# DIMM_CONNECTOR.net
KiCad netlist of a schematic drawn in Altium Designer
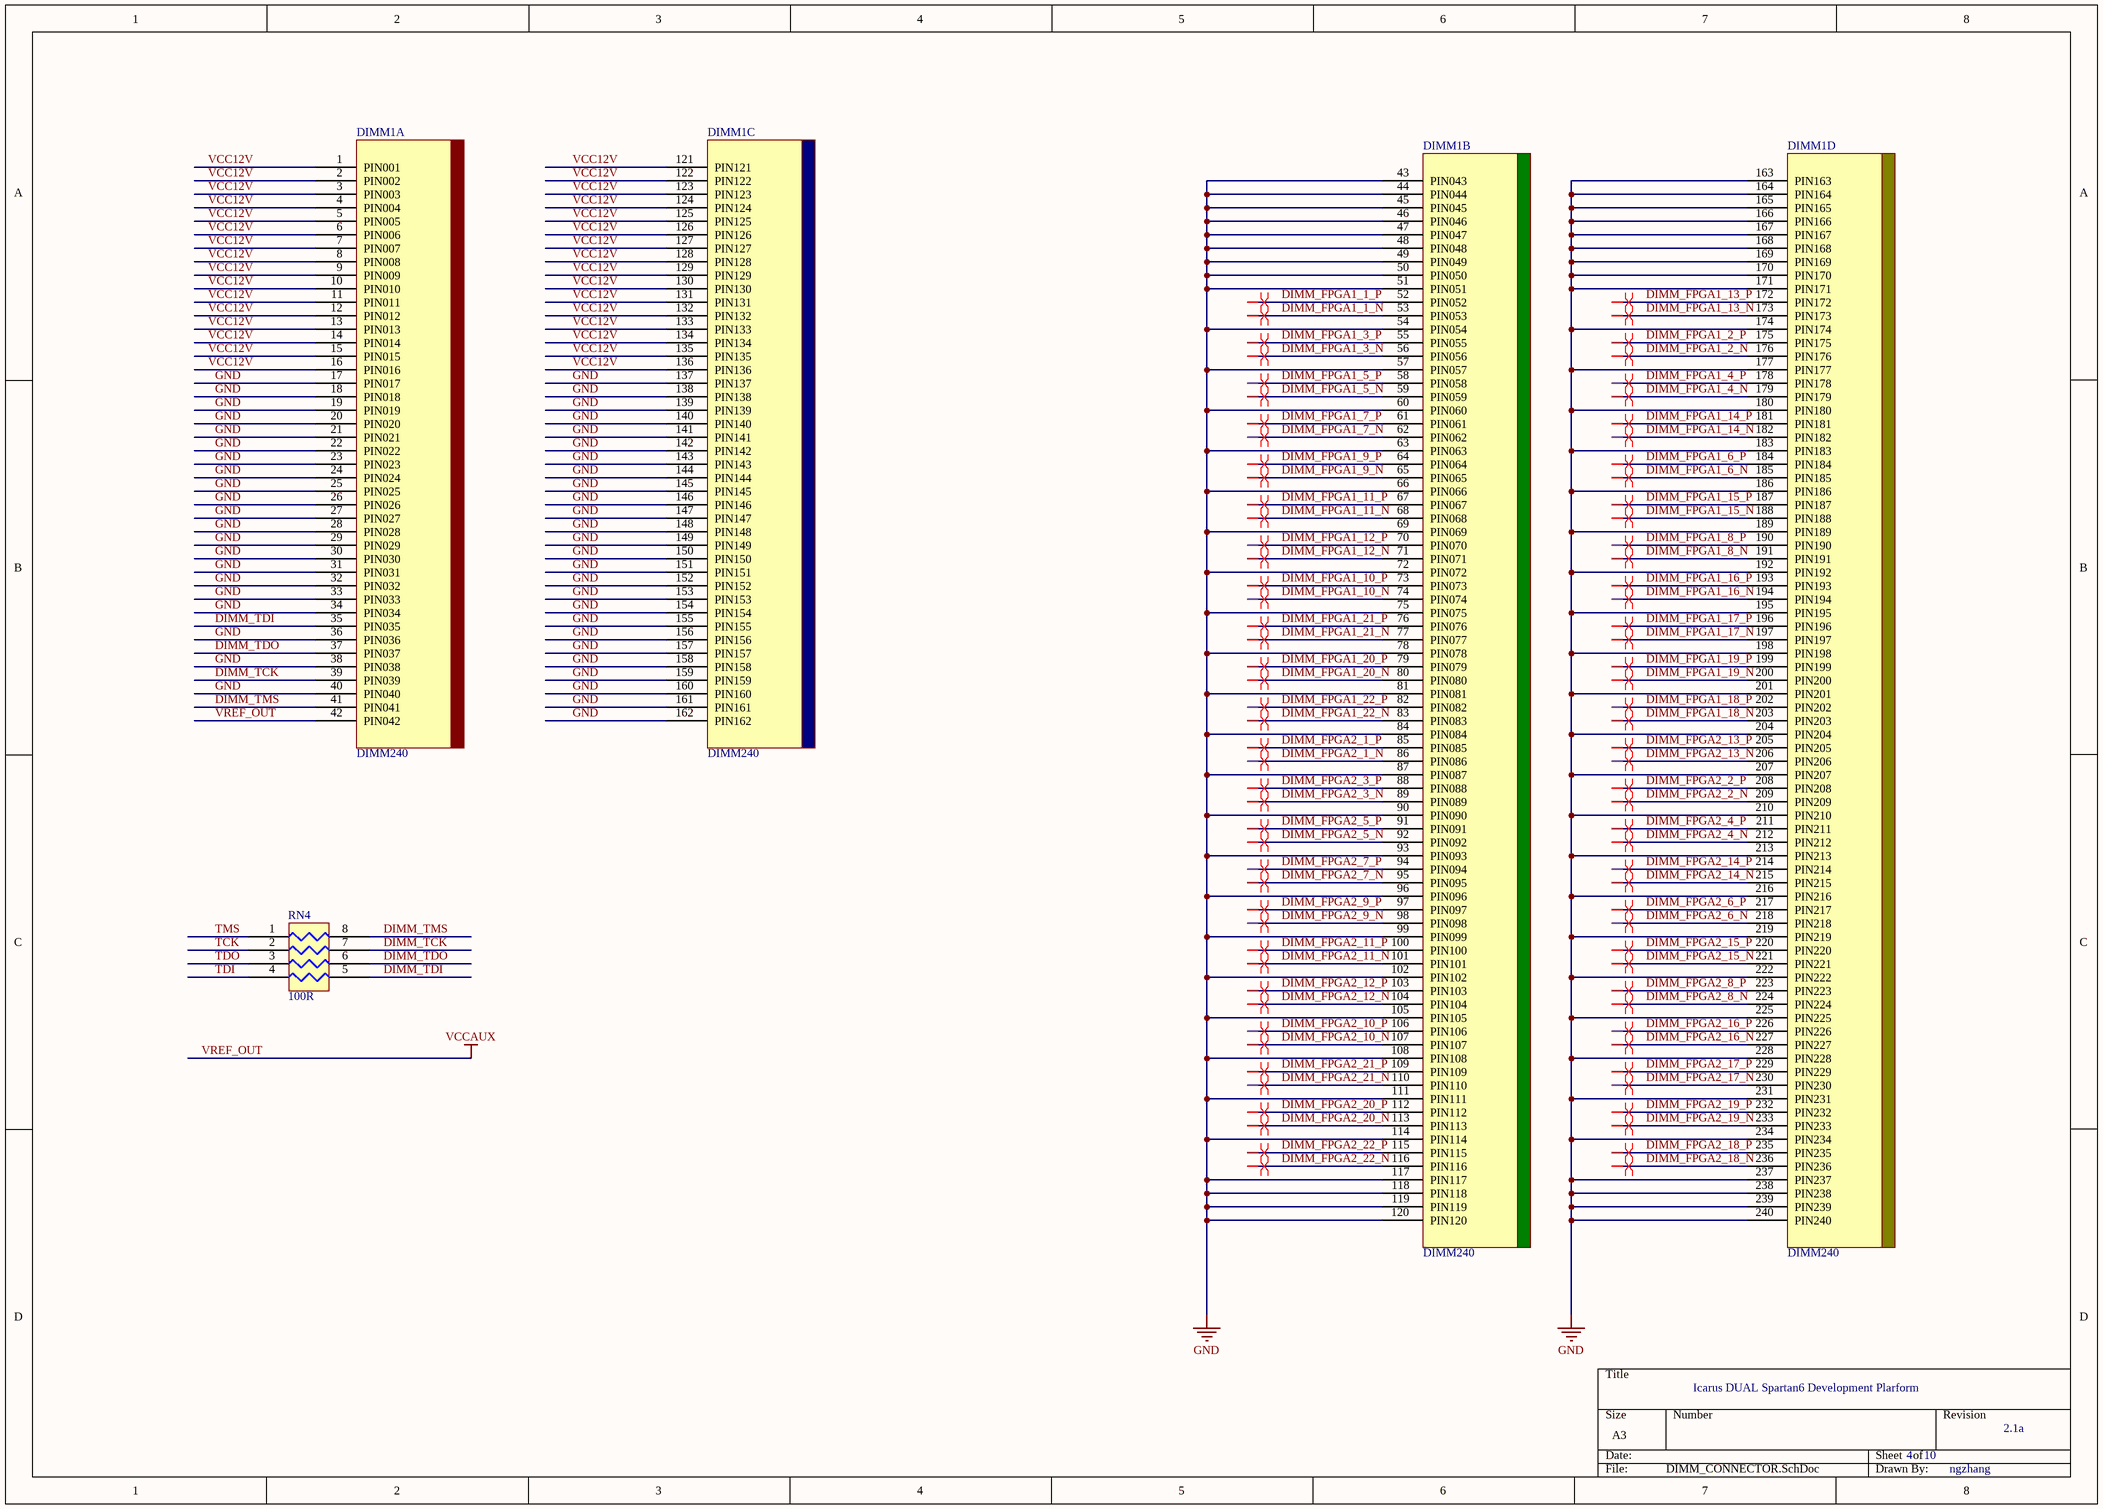
[diagram p0: DIMM_CONNECTOR.SchDoc]

(export (version "E")
  (design (tool "Eeschema 10.0.6"))
  (components
    (comp (ref "DIMM1") (value "DIMM240") (footprint "DIMM240") (libsource (lib "S6") (part "DIMM240")))
    (comp (ref "RN4") (value "100R") (footprint "EXBV8V") (libsource (lib "S6") (part "RES4PACK")))
  )
  (nets
    (net (code "1") (name "/DIMM_FPGA1_1_N") (class "Default")
      (node (ref "DIMM1") (pin "53") (pinfunction "PIN053_53") (pintype "power_in"))
    )
    (net (code "2") (name "/DIMM_FPGA1_1_P") (class "Default")
      (node (ref "DIMM1") (pin "52") (pinfunction "PIN052_52") (pintype "power_in"))
    )
    (net (code "3") (name "/DIMM_FPGA1_2_N") (class "Default")
      (node (ref "DIMM1") (pin "176") (pinfunction "PIN176_176") (pintype "power_in"))
    )
    (net (code "4") (name "/DIMM_FPGA1_2_P") (class "Default")
      (node (ref "DIMM1") (pin "175") (pinfunction "PIN175_175") (pintype "power_in"))
    )
    (net (code "5") (name "/DIMM_FPGA1_3_N") (class "Default")
      (node (ref "DIMM1") (pin "56") (pinfunction "PIN056_56") (pintype "power_in"))
    )
    (net (code "6") (name "/DIMM_FPGA1_3_P") (class "Default")
      (node (ref "DIMM1") (pin "55") (pinfunction "PIN055_55") (pintype "power_in"))
    )
    (net (code "7") (name "/DIMM_FPGA1_4_N") (class "Default")
      (node (ref "DIMM1") (pin "179") (pinfunction "PIN179_179") (pintype "power_in"))
    )
    (net (code "8") (name "/DIMM_FPGA1_4_P") (class "Default")
      (node (ref "DIMM1") (pin "178") (pinfunction "PIN178_178") (pintype "power_in"))
    )
    (net (code "9") (name "/DIMM_FPGA1_5_N") (class "Default")
      (node (ref "DIMM1") (pin "59") (pinfunction "PIN059_59") (pintype "power_in"))
    )
    (net (code "10") (name "/DIMM_FPGA1_5_P") (class "Default")
      (node (ref "DIMM1") (pin "58") (pinfunction "PIN058_58") (pintype "power_in"))
    )
    (net (code "11") (name "/DIMM_FPGA1_6_N") (class "Default")
      (node (ref "DIMM1") (pin "185") (pinfunction "PIN185_185") (pintype "power_in"))
    )
    (net (code "12") (name "/DIMM_FPGA1_6_P") (class "Default")
      (node (ref "DIMM1") (pin "184") (pinfunction "PIN184_184") (pintype "power_in"))
    )
    (net (code "13") (name "/DIMM_FPGA1_7_N") (class "Default")
      (node (ref "DIMM1") (pin "62") (pinfunction "PIN062_62") (pintype "power_in"))
    )
    (net (code "14") (name "/DIMM_FPGA1_7_P") (class "Default")
      (node (ref "DIMM1") (pin "61") (pinfunction "PIN061_61") (pintype "power_in"))
    )
    (net (code "15") (name "/DIMM_FPGA1_8_N") (class "Default")
      (node (ref "DIMM1") (pin "191") (pinfunction "PIN191_191") (pintype "power_in"))
    )
    (net (code "16") (name "/DIMM_FPGA1_8_P") (class "Default")
      (node (ref "DIMM1") (pin "190") (pinfunction "PIN190_190") (pintype "power_in"))
    )
    (net (code "17") (name "/DIMM_FPGA1_9_N") (class "Default")
      (node (ref "DIMM1") (pin "65") (pinfunction "PIN065_65") (pintype "power_in"))
    )
    (net (code "18") (name "/DIMM_FPGA1_9_P") (class "Default")
      (node (ref "DIMM1") (pin "64") (pinfunction "PIN064_64") (pintype "power_in"))
    )
    (net (code "19") (name "/DIMM_FPGA1_10_N") (class "Default")
      (node (ref "DIMM1") (pin "74") (pinfunction "PIN074_74") (pintype "power_in"))
    )
    (net (code "20") (name "/DIMM_FPGA1_10_P") (class "Default")
      (node (ref "DIMM1") (pin "73") (pinfunction "PIN073_73") (pintype "power_in"))
    )
    (net (code "21") (name "/DIMM_FPGA1_11_N") (class "Default")
      (node (ref "DIMM1") (pin "68") (pinfunction "PIN068_68") (pintype "power_in"))
    )
    (net (code "22") (name "/DIMM_FPGA1_11_P") (class "Default")
      (node (ref "DIMM1") (pin "67") (pinfunction "PIN067_67") (pintype "power_in"))
    )
    (net (code "23") (name "/DIMM_FPGA1_12_N") (class "Default")
      (node (ref "DIMM1") (pin "71") (pinfunction "PIN071_71") (pintype "power_in"))
    )
    (net (code "24") (name "/DIMM_FPGA1_12_P") (class "Default")
      (node (ref "DIMM1") (pin "70") (pinfunction "PIN070_70") (pintype "power_in"))
    )
    (net (code "25") (name "/DIMM_FPGA1_13_N") (class "Default")
      (node (ref "DIMM1") (pin "173") (pinfunction "PIN173_173") (pintype "power_in"))
    )
    (net (code "26") (name "/DIMM_FPGA1_13_P") (class "Default")
      (node (ref "DIMM1") (pin "172") (pinfunction "PIN172_172") (pintype "power_in"))
    )
    (net (code "27") (name "/DIMM_FPGA1_14_N") (class "Default")
      (node (ref "DIMM1") (pin "182") (pinfunction "PIN182_182") (pintype "power_in"))
    )
    (net (code "28") (name "/DIMM_FPGA1_14_P") (class "Default")
      (node (ref "DIMM1") (pin "181") (pinfunction "PIN181_181") (pintype "power_in"))
    )
    (net (code "29") (name "/DIMM_FPGA1_15_N") (class "Default")
      (node (ref "DIMM1") (pin "188") (pinfunction "PIN188_188") (pintype "power_in"))
    )
    (net (code "30") (name "/DIMM_FPGA1_15_P") (class "Default")
      (node (ref "DIMM1") (pin "187") (pinfunction "PIN187_187") (pintype "power_in"))
    )
    (net (code "31") (name "/DIMM_FPGA1_16_N") (class "Default")
      (node (ref "DIMM1") (pin "194") (pinfunction "PIN194_194") (pintype "power_in"))
    )
    (net (code "32") (name "/DIMM_FPGA1_16_P") (class "Default")
      (node (ref "DIMM1") (pin "193") (pinfunction "PIN193_193") (pintype "power_in"))
    )
    (net (code "33") (name "/DIMM_FPGA1_17_N") (class "Default")
      (node (ref "DIMM1") (pin "197") (pinfunction "PIN197_197") (pintype "power_in"))
    )
    (net (code "34") (name "/DIMM_FPGA1_17_P") (class "Default")
      (node (ref "DIMM1") (pin "196") (pinfunction "PIN196_196") (pintype "power_in"))
    )
    (net (code "35") (name "/DIMM_FPGA1_18_N") (class "Default")
      (node (ref "DIMM1") (pin "203") (pinfunction "PIN203_203") (pintype "power_in"))
    )
    (net (code "36") (name "/DIMM_FPGA1_18_P") (class "Default")
      (node (ref "DIMM1") (pin "202") (pinfunction "PIN202_202") (pintype "power_in"))
    )
    (net (code "37") (name "/DIMM_FPGA1_19_N") (class "Default")
      (node (ref "DIMM1") (pin "200") (pinfunction "PIN200_200") (pintype "power_in"))
    )
    (net (code "38") (name "/DIMM_FPGA1_19_P") (class "Default")
      (node (ref "DIMM1") (pin "199") (pinfunction "PIN199_199") (pintype "power_in"))
    )
    (net (code "39") (name "/DIMM_FPGA1_20_N") (class "Default")
      (node (ref "DIMM1") (pin "80") (pinfunction "PIN080_80") (pintype "power_in"))
    )
    (net (code "40") (name "/DIMM_FPGA1_20_P") (class "Default")
      (node (ref "DIMM1") (pin "79") (pinfunction "PIN079_79") (pintype "power_in"))
    )
    (net (code "41") (name "/DIMM_FPGA1_21_N") (class "Default")
      (node (ref "DIMM1") (pin "77") (pinfunction "PIN077_77") (pintype "power_in"))
    )
    (net (code "42") (name "/DIMM_FPGA1_21_P") (class "Default")
      (node (ref "DIMM1") (pin "76") (pinfunction "PIN076_76") (pintype "power_in"))
    )
    (net (code "43") (name "/DIMM_FPGA1_22_N") (class "Default")
      (node (ref "DIMM1") (pin "83") (pinfunction "PIN083_83") (pintype "power_in"))
    )
    (net (code "44") (name "/DIMM_FPGA1_22_P") (class "Default")
      (node (ref "DIMM1") (pin "82") (pinfunction "PIN082_82") (pintype "power_in"))
    )
    (net (code "45") (name "/DIMM_FPGA2_1_N") (class "Default")
      (node (ref "DIMM1") (pin "86") (pinfunction "PIN086_86") (pintype "power_in"))
    )
    (net (code "46") (name "/DIMM_FPGA2_1_P") (class "Default")
      (node (ref "DIMM1") (pin "85") (pinfunction "PIN085_85") (pintype "power_in"))
    )
    (net (code "47") (name "/DIMM_FPGA2_2_N") (class "Default")
      (node (ref "DIMM1") (pin "209") (pinfunction "PIN209_209") (pintype "power_in"))
    )
    (net (code "48") (name "/DIMM_FPGA2_2_P") (class "Default")
      (node (ref "DIMM1") (pin "208") (pinfunction "PIN208_208") (pintype "power_in"))
    )
    (net (code "49") (name "/DIMM_FPGA2_3_N") (class "Default")
      (node (ref "DIMM1") (pin "89") (pinfunction "PIN089_89") (pintype "power_in"))
    )
    (net (code "50") (name "/DIMM_FPGA2_3_P") (class "Default")
      (node (ref "DIMM1") (pin "88") (pinfunction "PIN088_88") (pintype "power_in"))
    )
    (net (code "51") (name "/DIMM_FPGA2_4_N") (class "Default")
      (node (ref "DIMM1") (pin "212") (pinfunction "PIN212_212") (pintype "power_in"))
    )
    (net (code "52") (name "/DIMM_FPGA2_4_P") (class "Default")
      (node (ref "DIMM1") (pin "211") (pinfunction "PIN211_211") (pintype "power_in"))
    )
    (net (code "53") (name "/DIMM_FPGA2_5_N") (class "Default")
      (node (ref "DIMM1") (pin "92") (pinfunction "PIN092_92") (pintype "power_in"))
    )
    (net (code "54") (name "/DIMM_FPGA2_5_P") (class "Default")
      (node (ref "DIMM1") (pin "91") (pinfunction "PIN091_91") (pintype "power_in"))
    )
    (net (code "55") (name "/DIMM_FPGA2_6_N") (class "Default")
      (node (ref "DIMM1") (pin "218") (pinfunction "PIN218_218") (pintype "power_in"))
    )
    (net (code "56") (name "/DIMM_FPGA2_6_P") (class "Default")
      (node (ref "DIMM1") (pin "217") (pinfunction "PIN217_217") (pintype "power_in"))
    )
    (net (code "57") (name "/DIMM_FPGA2_7_N") (class "Default")
      (node (ref "DIMM1") (pin "95") (pinfunction "PIN095_95") (pintype "power_in"))
    )
    (net (code "58") (name "/DIMM_FPGA2_7_P") (class "Default")
      (node (ref "DIMM1") (pin "94") (pinfunction "PIN094_94") (pintype "power_in"))
    )
    (net (code "59") (name "/DIMM_FPGA2_8_N") (class "Default")
      (node (ref "DIMM1") (pin "224") (pinfunction "PIN224_224") (pintype "power_in"))
    )
    (net (code "60") (name "/DIMM_FPGA2_8_P") (class "Default")
      (node (ref "DIMM1") (pin "223") (pinfunction "PIN223_223") (pintype "power_in"))
    )
    (net (code "61") (name "/DIMM_FPGA2_9_N") (class "Default")
      (node (ref "DIMM1") (pin "98") (pinfunction "PIN098_98") (pintype "power_in"))
    )
    (net (code "62") (name "/DIMM_FPGA2_9_P") (class "Default")
      (node (ref "DIMM1") (pin "97") (pinfunction "PIN097_97") (pintype "power_in"))
    )
    (net (code "63") (name "/DIMM_FPGA2_10_N") (class "Default")
      (node (ref "DIMM1") (pin "107") (pinfunction "PIN107_107") (pintype "power_in"))
    )
    (net (code "64") (name "/DIMM_FPGA2_10_P") (class "Default")
      (node (ref "DIMM1") (pin "106") (pinfunction "PIN106_106") (pintype "power_in"))
    )
    (net (code "65") (name "/DIMM_FPGA2_11_N") (class "Default")
      (node (ref "DIMM1") (pin "101") (pinfunction "PIN101_101") (pintype "power_in"))
    )
    (net (code "66") (name "/DIMM_FPGA2_11_P") (class "Default")
      (node (ref "DIMM1") (pin "100") (pinfunction "PIN100_100") (pintype "power_in"))
    )
    (net (code "67") (name "/DIMM_FPGA2_12_N") (class "Default")
      (node (ref "DIMM1") (pin "104") (pinfunction "PIN104_104") (pintype "power_in"))
    )
    (net (code "68") (name "/DIMM_FPGA2_12_P") (class "Default")
      (node (ref "DIMM1") (pin "103") (pinfunction "PIN103_103") (pintype "power_in"))
    )
    (net (code "69") (name "/DIMM_FPGA2_13_N") (class "Default")
      (node (ref "DIMM1") (pin "206") (pinfunction "PIN206_206") (pintype "power_in"))
    )
    (net (code "70") (name "/DIMM_FPGA2_13_P") (class "Default")
      (node (ref "DIMM1") (pin "205") (pinfunction "PIN205_205") (pintype "power_in"))
    )
    (net (code "71") (name "/DIMM_FPGA2_14_N") (class "Default")
      (node (ref "DIMM1") (pin "215") (pinfunction "PIN215_215") (pintype "power_in"))
    )
    (net (code "72") (name "/DIMM_FPGA2_14_P") (class "Default")
      (node (ref "DIMM1") (pin "214") (pinfunction "PIN214_214") (pintype "power_in"))
    )
    (net (code "73") (name "/DIMM_FPGA2_15_N") (class "Default")
      (node (ref "DIMM1") (pin "221") (pinfunction "PIN221_221") (pintype "power_in"))
    )
    (net (code "74") (name "/DIMM_FPGA2_15_P") (class "Default")
      (node (ref "DIMM1") (pin "220") (pinfunction "PIN220_220") (pintype "power_in"))
    )
    (net (code "75") (name "/DIMM_FPGA2_16_N") (class "Default")
      (node (ref "DIMM1") (pin "227") (pinfunction "PIN227_227") (pintype "power_in"))
    )
    (net (code "76") (name "/DIMM_FPGA2_16_P") (class "Default")
      (node (ref "DIMM1") (pin "226") (pinfunction "PIN226_226") (pintype "power_in"))
    )
    (net (code "77") (name "/DIMM_FPGA2_17_N") (class "Default")
      (node (ref "DIMM1") (pin "230") (pinfunction "PIN230_230") (pintype "power_in"))
    )
    (net (code "78") (name "/DIMM_FPGA2_17_P") (class "Default")
      (node (ref "DIMM1") (pin "229") (pinfunction "PIN229_229") (pintype "power_in"))
    )
    (net (code "79") (name "/DIMM_FPGA2_18_N") (class "Default")
      (node (ref "DIMM1") (pin "236") (pinfunction "PIN236_236") (pintype "power_in"))
    )
    (net (code "80") (name "/DIMM_FPGA2_18_P") (class "Default")
      (node (ref "DIMM1") (pin "235") (pinfunction "PIN235_235") (pintype "power_in"))
    )
    (net (code "81") (name "/DIMM_FPGA2_19_N") (class "Default")
      (node (ref "DIMM1") (pin "233") (pinfunction "PIN233_233") (pintype "power_in"))
    )
    (net (code "82") (name "/DIMM_FPGA2_19_P") (class "Default")
      (node (ref "DIMM1") (pin "232") (pinfunction "PIN232_232") (pintype "power_in"))
    )
    (net (code "83") (name "/DIMM_FPGA2_20_N") (class "Default")
      (node (ref "DIMM1") (pin "113") (pinfunction "PIN113_113") (pintype "power_in"))
    )
    (net (code "84") (name "/DIMM_FPGA2_20_P") (class "Default")
      (node (ref "DIMM1") (pin "112") (pinfunction "PIN112_112") (pintype "power_in"))
    )
    (net (code "85") (name "/DIMM_FPGA2_21_N") (class "Default")
      (node (ref "DIMM1") (pin "110") (pinfunction "PIN110_110") (pintype "power_in"))
    )
    (net (code "86") (name "/DIMM_FPGA2_21_P") (class "Default")
      (node (ref "DIMM1") (pin "109") (pinfunction "PIN109_109") (pintype "power_in"))
    )
    (net (code "87") (name "/DIMM_FPGA2_22_N") (class "Default")
      (node (ref "DIMM1") (pin "116") (pinfunction "PIN116_116") (pintype "power_in"))
    )
    (net (code "88") (name "/DIMM_FPGA2_22_P") (class "Default")
      (node (ref "DIMM1") (pin "115") (pinfunction "PIN115_115") (pintype "power_in"))
    )
    (net (code "89") (name "/DIMM_TCK") (class "Default")
      (node (ref "DIMM1") (pin "39") (pinfunction "PIN039_39") (pintype "power_in"))
      (node (ref "RN4") (pin "7") (pinfunction "7_7") (pintype "power_in"))
    )
    (net (code "90") (name "/DIMM_TDI") (class "Default")
      (node (ref "DIMM1") (pin "35") (pinfunction "PIN035_35") (pintype "power_in"))
      (node (ref "RN4") (pin "5") (pinfunction "5_5") (pintype "power_in"))
    )
    (net (code "91") (name "/DIMM_TDO") (class "Default")
      (node (ref "DIMM1") (pin "37") (pinfunction "PIN037_37") (pintype "power_in"))
      (node (ref "RN4") (pin "6") (pinfunction "6_6") (pintype "power_in"))
    )
    (net (code "92") (name "/DIMM_TMS") (class "Default")
      (node (ref "DIMM1") (pin "41") (pinfunction "PIN041_41") (pintype "power_in"))
      (node (ref "RN4") (pin "8") (pinfunction "8_8") (pintype "power_in"))
    )
    (net (code "93") (name "/TCK") (class "Default")
      (node (ref "RN4") (pin "2") (pinfunction "2_2") (pintype "power_in"))
    )
    (net (code "94") (name "/TDI") (class "Default")
      (node (ref "RN4") (pin "4") (pinfunction "4_4") (pintype "power_in"))
    )
    (net (code "95") (name "/TDO") (class "Default")
      (node (ref "RN4") (pin "3") (pinfunction "3_3") (pintype "power_in"))
    )
    (net (code "96") (name "/TMS") (class "Default")
      (node (ref "RN4") (pin "1") (pinfunction "1_1") (pintype "power_in"))
    )
    (net (code "97") (name "/VCC12V") (class "Default")
      (node (ref "DIMM1") (pin "1") (pinfunction "PIN001_1") (pintype "power_in"))
      (node (ref "DIMM1") (pin "10") (pinfunction "PIN010_10") (pintype "power_in"))
      (node (ref "DIMM1") (pin "11") (pinfunction "PIN011_11") (pintype "power_in"))
      (node (ref "DIMM1") (pin "12") (pinfunction "PIN012_12") (pintype "power_in"))
      (node (ref "DIMM1") (pin "121") (pinfunction "PIN121_121") (pintype "power_in"))
      (node (ref "DIMM1") (pin "122") (pinfunction "PIN122_122") (pintype "power_in"))
      (node (ref "DIMM1") (pin "123") (pinfunction "PIN123_123") (pintype "power_in"))
      (node (ref "DIMM1") (pin "124") (pinfunction "PIN124_124") (pintype "power_in"))
      (node (ref "DIMM1") (pin "125") (pinfunction "PIN125_125") (pintype "power_in"))
      (node (ref "DIMM1") (pin "126") (pinfunction "PIN126_126") (pintype "power_in"))
      (node (ref "DIMM1") (pin "127") (pinfunction "PIN127_127") (pintype "power_in"))
      (node (ref "DIMM1") (pin "128") (pinfunction "PIN128_128") (pintype "power_in"))
      (node (ref "DIMM1") (pin "129") (pinfunction "PIN129_129") (pintype "power_in"))
      (node (ref "DIMM1") (pin "13") (pinfunction "PIN013_13") (pintype "power_in"))
      (node (ref "DIMM1") (pin "130") (pinfunction "PIN130_130") (pintype "power_in"))
      (node (ref "DIMM1") (pin "131") (pinfunction "PIN131_131") (pintype "power_in"))
      (node (ref "DIMM1") (pin "132") (pinfunction "PIN132_132") (pintype "power_in"))
      (node (ref "DIMM1") (pin "133") (pinfunction "PIN133_133") (pintype "power_in"))
      (node (ref "DIMM1") (pin "134") (pinfunction "PIN134_134") (pintype "power_in"))
      (node (ref "DIMM1") (pin "135") (pinfunction "PIN135_135") (pintype "power_in"))
      (node (ref "DIMM1") (pin "136") (pinfunction "PIN136_136") (pintype "power_in"))
      (node (ref "DIMM1") (pin "14") (pinfunction "PIN014_14") (pintype "power_in"))
      (node (ref "DIMM1") (pin "15") (pinfunction "PIN015_15") (pintype "power_in"))
      (node (ref "DIMM1") (pin "16") (pinfunction "PIN016_16") (pintype "power_in"))
      (node (ref "DIMM1") (pin "2") (pinfunction "PIN002_2") (pintype "power_in"))
      (node (ref "DIMM1") (pin "3") (pinfunction "PIN003_3") (pintype "power_in"))
      (node (ref "DIMM1") (pin "4") (pinfunction "PIN004_4") (pintype "power_in"))
      (node (ref "DIMM1") (pin "5") (pinfunction "PIN005_5") (pintype "power_in"))
      (node (ref "DIMM1") (pin "6") (pinfunction "PIN006_6") (pintype "power_in"))
      (node (ref "DIMM1") (pin "7") (pinfunction "PIN007_7") (pintype "power_in"))
      (node (ref "DIMM1") (pin "8") (pinfunction "PIN008_8") (pintype "power_in"))
      (node (ref "DIMM1") (pin "9") (pinfunction "PIN009_9") (pintype "power_in"))
    )
    (net (code "98") (name "GND") (class "Default")
      (node (ref "DIMM1") (pin "102") (pinfunction "PIN102_102") (pintype "power_in"))
      (node (ref "DIMM1") (pin "105") (pinfunction "PIN105_105") (pintype "power_in"))
      (node (ref "DIMM1") (pin "108") (pinfunction "PIN108_108") (pintype "power_in"))
      (node (ref "DIMM1") (pin "111") (pinfunction "PIN111_111") (pintype "power_in"))
      (node (ref "DIMM1") (pin "114") (pinfunction "PIN114_114") (pintype "power_in"))
      (node (ref "DIMM1") (pin "117") (pinfunction "PIN117_117") (pintype "power_in"))
      (node (ref "DIMM1") (pin "118") (pinfunction "PIN118_118") (pintype "power_in"))
      (node (ref "DIMM1") (pin "119") (pinfunction "PIN119_119") (pintype "power_in"))
      (node (ref "DIMM1") (pin "120") (pinfunction "PIN120_120") (pintype "power_in"))
      (node (ref "DIMM1") (pin "137") (pinfunction "PIN137_137") (pintype "power_in"))
      (node (ref "DIMM1") (pin "138") (pinfunction "PIN138_138") (pintype "power_in"))
      (node (ref "DIMM1") (pin "139") (pinfunction "PIN139_139") (pintype "power_in"))
      (node (ref "DIMM1") (pin "140") (pinfunction "PIN140_140") (pintype "power_in"))
      (node (ref "DIMM1") (pin "141") (pinfunction "PIN141_141") (pintype "power_in"))
      (node (ref "DIMM1") (pin "142") (pinfunction "PIN142_142") (pintype "power_in"))
      (node (ref "DIMM1") (pin "143") (pinfunction "PIN143_143") (pintype "power_in"))
      (node (ref "DIMM1") (pin "144") (pinfunction "PIN144_144") (pintype "power_in"))
      (node (ref "DIMM1") (pin "145") (pinfunction "PIN145_145") (pintype "power_in"))
      (node (ref "DIMM1") (pin "146") (pinfunction "PIN146_146") (pintype "power_in"))
      (node (ref "DIMM1") (pin "147") (pinfunction "PIN147_147") (pintype "power_in"))
      (node (ref "DIMM1") (pin "148") (pinfunction "PIN148_148") (pintype "power_in"))
      (node (ref "DIMM1") (pin "149") (pinfunction "PIN149_149") (pintype "power_in"))
      (node (ref "DIMM1") (pin "150") (pinfunction "PIN150_150") (pintype "power_in"))
      (node (ref "DIMM1") (pin "151") (pinfunction "PIN151_151") (pintype "power_in"))
      (node (ref "DIMM1") (pin "152") (pinfunction "PIN152_152") (pintype "power_in"))
      (node (ref "DIMM1") (pin "153") (pinfunction "PIN153_153") (pintype "power_in"))
      (node (ref "DIMM1") (pin "154") (pinfunction "PIN154_154") (pintype "power_in"))
      (node (ref "DIMM1") (pin "155") (pinfunction "PIN155_155") (pintype "power_in"))
      (node (ref "DIMM1") (pin "156") (pinfunction "PIN156_156") (pintype "power_in"))
      (node (ref "DIMM1") (pin "157") (pinfunction "PIN157_157") (pintype "power_in"))
      (node (ref "DIMM1") (pin "158") (pinfunction "PIN158_158") (pintype "power_in"))
      (node (ref "DIMM1") (pin "159") (pinfunction "PIN159_159") (pintype "power_in"))
      (node (ref "DIMM1") (pin "160") (pinfunction "PIN160_160") (pintype "power_in"))
      (node (ref "DIMM1") (pin "161") (pinfunction "PIN161_161") (pintype "power_in"))
      (node (ref "DIMM1") (pin "162") (pinfunction "PIN162_162") (pintype "power_in"))
      (node (ref "DIMM1") (pin "163") (pinfunction "PIN163_163") (pintype "power_in"))
      (node (ref "DIMM1") (pin "164") (pinfunction "PIN164_164") (pintype "power_in"))
      (node (ref "DIMM1") (pin "165") (pinfunction "PIN165_165") (pintype "power_in"))
      (node (ref "DIMM1") (pin "166") (pinfunction "PIN166_166") (pintype "power_in"))
      (node (ref "DIMM1") (pin "167") (pinfunction "PIN167_167") (pintype "power_in"))
      (node (ref "DIMM1") (pin "168") (pinfunction "PIN168_168") (pintype "power_in"))
      (node (ref "DIMM1") (pin "169") (pinfunction "PIN169_169") (pintype "power_in"))
      (node (ref "DIMM1") (pin "17") (pinfunction "PIN017_17") (pintype "power_in"))
      (node (ref "DIMM1") (pin "170") (pinfunction "PIN170_170") (pintype "power_in"))
      (node (ref "DIMM1") (pin "171") (pinfunction "PIN171_171") (pintype "power_in"))
      (node (ref "DIMM1") (pin "174") (pinfunction "PIN174_174") (pintype "power_in"))
      (node (ref "DIMM1") (pin "177") (pinfunction "PIN177_177") (pintype "power_in"))
      (node (ref "DIMM1") (pin "18") (pinfunction "PIN018_18") (pintype "power_in"))
      (node (ref "DIMM1") (pin "180") (pinfunction "PIN180_180") (pintype "power_in"))
      (node (ref "DIMM1") (pin "183") (pinfunction "PIN183_183") (pintype "power_in"))
      (node (ref "DIMM1") (pin "186") (pinfunction "PIN186_186") (pintype "power_in"))
      (node (ref "DIMM1") (pin "189") (pinfunction "PIN189_189") (pintype "power_in"))
      (node (ref "DIMM1") (pin "19") (pinfunction "PIN019_19") (pintype "power_in"))
      (node (ref "DIMM1") (pin "192") (pinfunction "PIN192_192") (pintype "power_in"))
      (node (ref "DIMM1") (pin "195") (pinfunction "PIN195_195") (pintype "power_in"))
      (node (ref "DIMM1") (pin "198") (pinfunction "PIN198_198") (pintype "power_in"))
      (node (ref "DIMM1") (pin "20") (pinfunction "PIN020_20") (pintype "power_in"))
      (node (ref "DIMM1") (pin "201") (pinfunction "PIN201_201") (pintype "power_in"))
      (node (ref "DIMM1") (pin "204") (pinfunction "PIN204_204") (pintype "power_in"))
      (node (ref "DIMM1") (pin "207") (pinfunction "PIN207_207") (pintype "power_in"))
      (node (ref "DIMM1") (pin "21") (pinfunction "PIN021_21") (pintype "power_in"))
      (node (ref "DIMM1") (pin "210") (pinfunction "PIN210_210") (pintype "power_in"))
      (node (ref "DIMM1") (pin "213") (pinfunction "PIN213_213") (pintype "power_in"))
      (node (ref "DIMM1") (pin "216") (pinfunction "PIN216_216") (pintype "power_in"))
      (node (ref "DIMM1") (pin "219") (pinfunction "PIN219_219") (pintype "power_in"))
      (node (ref "DIMM1") (pin "22") (pinfunction "PIN022_22") (pintype "power_in"))
      (node (ref "DIMM1") (pin "222") (pinfunction "PIN222_222") (pintype "power_in"))
      (node (ref "DIMM1") (pin "225") (pinfunction "PIN225_225") (pintype "power_in"))
      (node (ref "DIMM1") (pin "228") (pinfunction "PIN228_228") (pintype "power_in"))
      (node (ref "DIMM1") (pin "23") (pinfunction "PIN023_23") (pintype "power_in"))
      (node (ref "DIMM1") (pin "231") (pinfunction "PIN231_231") (pintype "power_in"))
      (node (ref "DIMM1") (pin "234") (pinfunction "PIN234_234") (pintype "power_in"))
      (node (ref "DIMM1") (pin "237") (pinfunction "PIN237_237") (pintype "power_in"))
      (node (ref "DIMM1") (pin "238") (pinfunction "PIN238_238") (pintype "power_in"))
      (node (ref "DIMM1") (pin "239") (pinfunction "PIN239_239") (pintype "power_in"))
      (node (ref "DIMM1") (pin "24") (pinfunction "PIN024_24") (pintype "power_in"))
      (node (ref "DIMM1") (pin "240") (pinfunction "PIN240_240") (pintype "power_in"))
      (node (ref "DIMM1") (pin "25") (pinfunction "PIN025_25") (pintype "power_in"))
      (node (ref "DIMM1") (pin "26") (pinfunction "PIN026_26") (pintype "power_in"))
      (node (ref "DIMM1") (pin "27") (pinfunction "PIN027_27") (pintype "power_in"))
      (node (ref "DIMM1") (pin "28") (pinfunction "PIN028_28") (pintype "power_in"))
      (node (ref "DIMM1") (pin "29") (pinfunction "PIN029_29") (pintype "power_in"))
      (node (ref "DIMM1") (pin "30") (pinfunction "PIN030_30") (pintype "power_in"))
      (node (ref "DIMM1") (pin "31") (pinfunction "PIN031_31") (pintype "power_in"))
      (node (ref "DIMM1") (pin "32") (pinfunction "PIN032_32") (pintype "power_in"))
      (node (ref "DIMM1") (pin "33") (pinfunction "PIN033_33") (pintype "power_in"))
      (node (ref "DIMM1") (pin "34") (pinfunction "PIN034_34") (pintype "power_in"))
      (node (ref "DIMM1") (pin "36") (pinfunction "PIN036_36") (pintype "power_in"))
      (node (ref "DIMM1") (pin "38") (pinfunction "PIN038_38") (pintype "power_in"))
      (node (ref "DIMM1") (pin "40") (pinfunction "PIN040_40") (pintype "power_in"))
      (node (ref "DIMM1") (pin "43") (pinfunction "PIN043_43") (pintype "power_in"))
      (node (ref "DIMM1") (pin "44") (pinfunction "PIN044_44") (pintype "power_in"))
      (node (ref "DIMM1") (pin "45") (pinfunction "PIN045_45") (pintype "power_in"))
      (node (ref "DIMM1") (pin "46") (pinfunction "PIN046_46") (pintype "power_in"))
      (node (ref "DIMM1") (pin "47") (pinfunction "PIN047_47") (pintype "power_in"))
      (node (ref "DIMM1") (pin "48") (pinfunction "PIN048_48") (pintype "power_in"))
      (node (ref "DIMM1") (pin "49") (pinfunction "PIN049_49") (pintype "power_in"))
      (node (ref "DIMM1") (pin "50") (pinfunction "PIN050_50") (pintype "power_in"))
      (node (ref "DIMM1") (pin "51") (pinfunction "PIN051_51") (pintype "power_in"))
      (node (ref "DIMM1") (pin "54") (pinfunction "PIN054_54") (pintype "power_in"))
      (node (ref "DIMM1") (pin "57") (pinfunction "PIN057_57") (pintype "power_in"))
      (node (ref "DIMM1") (pin "60") (pinfunction "PIN060_60") (pintype "power_in"))
      (node (ref "DIMM1") (pin "63") (pinfunction "PIN063_63") (pintype "power_in"))
      (node (ref "DIMM1") (pin "66") (pinfunction "PIN066_66") (pintype "power_in"))
      (node (ref "DIMM1") (pin "69") (pinfunction "PIN069_69") (pintype "power_in"))
      (node (ref "DIMM1") (pin "72") (pinfunction "PIN072_72") (pintype "power_in"))
      (node (ref "DIMM1") (pin "75") (pinfunction "PIN075_75") (pintype "power_in"))
      (node (ref "DIMM1") (pin "78") (pinfunction "PIN078_78") (pintype "power_in"))
      (node (ref "DIMM1") (pin "81") (pinfunction "PIN081_81") (pintype "power_in"))
      (node (ref "DIMM1") (pin "84") (pinfunction "PIN084_84") (pintype "power_in"))
      (node (ref "DIMM1") (pin "87") (pinfunction "PIN087_87") (pintype "power_in"))
      (node (ref "DIMM1") (pin "90") (pinfunction "PIN090_90") (pintype "power_in"))
      (node (ref "DIMM1") (pin "93") (pinfunction "PIN093_93") (pintype "power_in"))
      (node (ref "DIMM1") (pin "96") (pinfunction "PIN096_96") (pintype "power_in"))
      (node (ref "DIMM1") (pin "99") (pinfunction "PIN099_99") (pintype "power_in"))
    )
    (net (code "99") (name "VCCAUX") (class "Default")
      (node (ref "DIMM1") (pin "42") (pinfunction "PIN042_42") (pintype "power_in"))
    )
  )
)
